# schematic.net
KiCad netlist of a schematic drawn in EAGLE
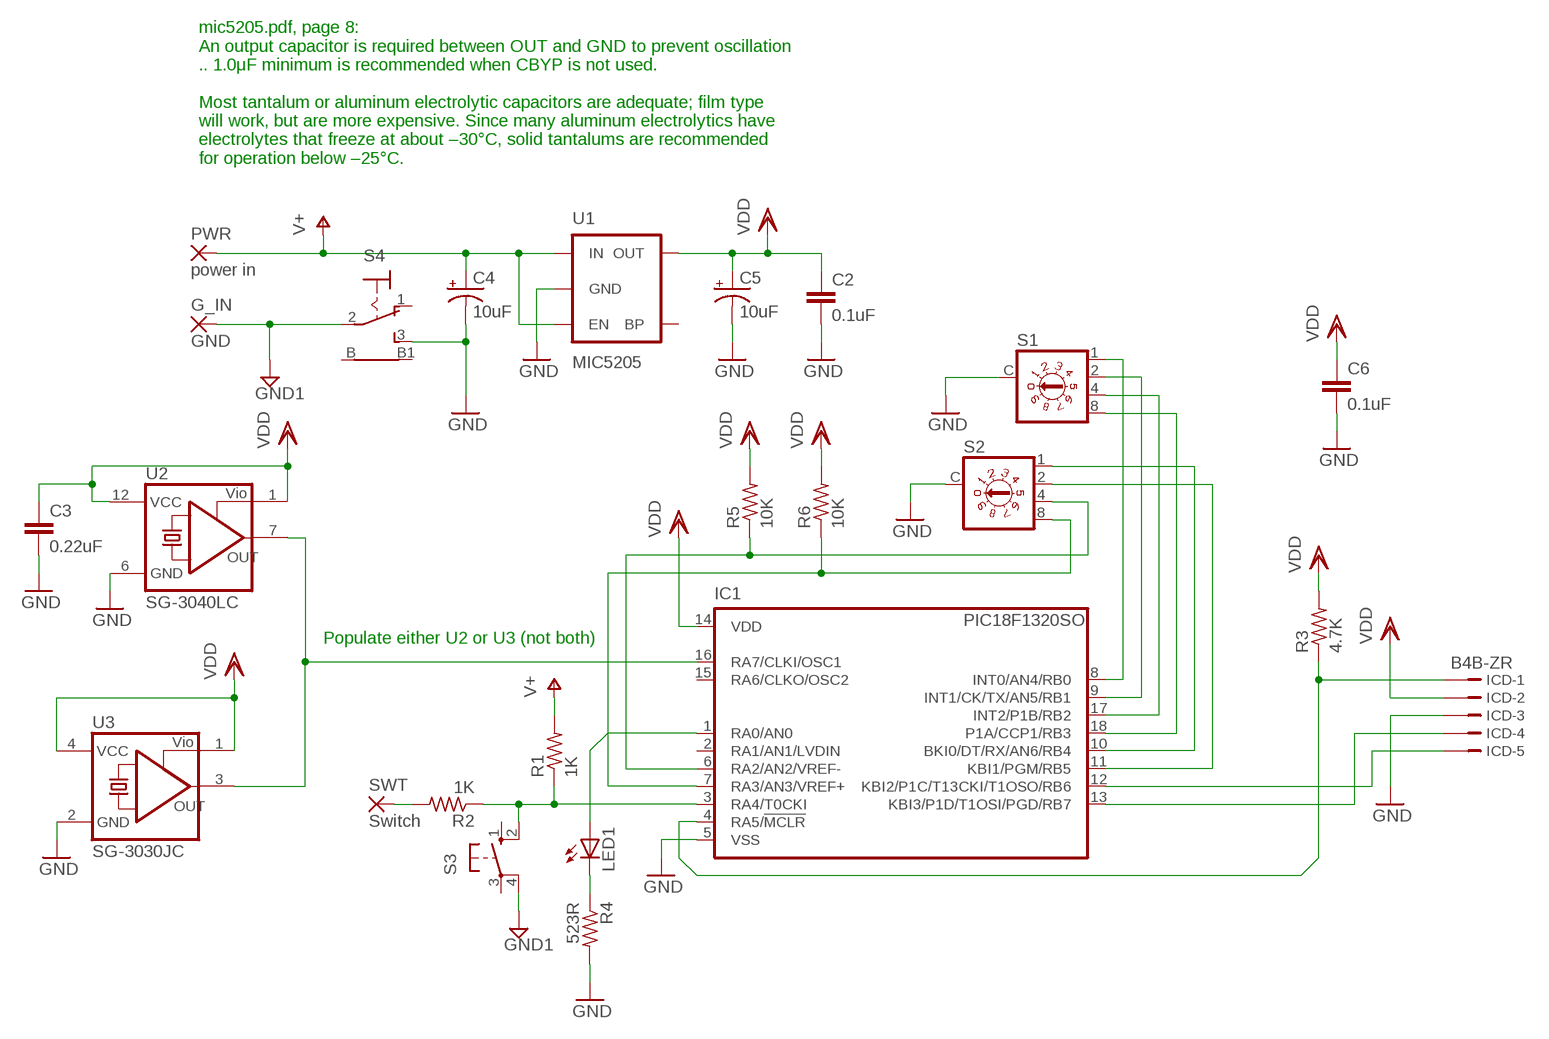
[diagram p0: schematic, sheet 1]

(export (version "E")
  (design (tool "Eeschema 10.0.6"))
  (components
    (comp (ref "C2")
      (value "0.1uF")
      (footprint "eagle-import:C2.5-3")
      (libsource (lib "eagle-import") (part "C2,5-3"))
    )
    (comp (ref "C3")
      (value "0.22uF")
      (footprint "eagle-import:C2.5-3")
      (libsource (lib "eagle-import") (part "C2,5-3"))
    )
    (comp (ref "C4")
      (value "10uF")
      (footprint "eagle-import:EIA3216")
      (libsource (lib "eagle-import") (part "CAP_POL1206"))
    )
    (comp (ref "C5")
      (value "10uF")
      (footprint "eagle-import:EIA3216")
      (libsource (lib "eagle-import") (part "CAP_POL1206"))
    )
    (comp (ref "C6")
      (value "0.1uF")
      (footprint "eagle-import:C2.5-3")
      (libsource (lib "eagle-import") (part "C2,5-3"))
    )
    (comp (ref "G_IN")
      (value "GND")
      (footprint "eagle-import:2,15_1,0")
      (libsource (lib "eagle-import") (part "2,15/1,0"))
    )
    (comp (ref "IC1")
      (value "PIC18F1320SO")
      (footprint "eagle-import:SO-18W")
      (fields (field (name "MF") "MICROCHIP") (field (name "MPN") "PIC18F1220-I/SO"))
      (libsource (lib "eagle-import") (part "PIC18F120SO2"))
    )
    (comp (ref "ICD")
      (value "B4B-ZR")
      (footprint "eagle-import:B5B-EH")
      (fields (field (name "MF") "FARNELL") (field (name "MPN") "B4B-ZR(LF)(SN)"))
      (libsource (lib "eagle-import") (part "?4B-ZRB"))
    )
    (comp (ref "LED1")
      (value "LED3MM")
      (footprint "eagle-import:LED3MM")
      (libsource (lib "eagle-import") (part "LED3MM"))
    )
    (comp (ref "PWR")
      (value "power in")
      (footprint "eagle-import:2,15_1,0")
      (libsource (lib "eagle-import") (part "2,15/1,0"))
    )
    (comp (ref "R1")
      (value "1K")
      (footprint "eagle-import:0204V")
      (libsource (lib "eagle-import") (part "R-US_0204/2V"))
    )
    (comp (ref "R2")
      (value "1K")
      (footprint "eagle-import:0204V")
      (libsource (lib "eagle-import") (part "R-US_0204/2V"))
    )
    (comp (ref "R3")
      (value "4.7K")
      (footprint "eagle-import:0204V")
      (libsource (lib "eagle-import") (part "R-US_0204/2V"))
    )
    (comp (ref "R4")
      (value "523R")
      (footprint "eagle-import:0204V")
      (libsource (lib "eagle-import") (part "R-US_0204/2V"))
    )
    (comp (ref "R5")
      (value "10K")
      (footprint "eagle-import:0204V")
      (libsource (lib "eagle-import") (part "R-US_0204/2V"))
    )
    (comp (ref "R6")
      (value "10K")
      (footprint "eagle-import:0204V")
      (libsource (lib "eagle-import") (part "R-US_0204/2V"))
    )
    (comp (ref "S1")
      (value "P101")
      (footprint "eagle-import:P101")
      (libsource (lib "eagle-import") (part "P101"))
    )
    (comp (ref "S2")
      (value "P101")
      (footprint "eagle-import:P101")
      (libsource (lib "eagle-import") (part "P101"))
    )
    (comp (ref "S3")
      (value "10-XX")
      (footprint "eagle-import:B3F-10XX")
      (fields (field (name "MPN") "B3F-1000"))
      (libsource (lib "eagle-import") (part "10-XX"))
    )
    (comp (ref "S4")
      (value "C&K_E101")
      (footprint "eagle-import:C&K_E101MD1ABE")
      (libsource (lib "eagle-import") (part "C&K_E101"))
    )
    (comp (ref "SWT")
      (value "Switch")
      (footprint "eagle-import:2,15_1,0")
      (libsource (lib "eagle-import") (part "2,15/1,0"))
    )
    (comp (ref "U1")
      (value "MIC5205")
      (footprint "eagle-import:SOT23-5")
      (libsource (lib "eagle-import") (part "V_REG_LDOSMD"))
    )
    (comp (ref "U2")
      (value "SG-3040LC")
      (footprint "eagle-import:SOJ-12-L")
      (libsource (lib "eagle-import") (part "SG-3030,40(LC,JC,JF)LC-LARGE"))
    )
    (comp (ref "U3")
      (value "SG-3030JC")
      (footprint "eagle-import:JC_TYPE")
      (libsource (lib "eagle-import") (part "SG-3030,40(LC,JC,JF)JC"))
    )
  )
  (nets
    (net (code "1") (name "GND") (class "Default")
      (node (ref "C2") (pin "2") (pinfunction "2_2") (pintype "passive"))
      (node (ref "C3") (pin "2") (pinfunction "2_2") (pintype "passive"))
      (node (ref "C4") (pin "C") (pinfunction "-_C") (pintype "passive"))
      (node (ref "C5") (pin "C") (pinfunction "-_C") (pintype "passive"))
      (node (ref "C6") (pin "2") (pinfunction "2_2") (pintype "passive"))
      (node (ref "IC1") (pin "5") (pinfunction "VSS_5") (pintype "power_in"))
      (node (ref "ICD") (pin "3") (pinfunction "1_3") (pintype "passive"))
      (node (ref "R4") (pin "2") (pinfunction "2_2") (pintype "passive"))
      (node (ref "S1") (pin "C") (pinfunction "C_C") (pintype "passive"))
      (node (ref "S2") (pin "C") (pinfunction "C_C") (pintype "passive"))
      (node (ref "S4") (pin "3") (pinfunction "S_3") (pintype "passive"))
      (node (ref "U1") (pin "2") (pinfunction "GND_2") (pintype "input"))
      (node (ref "U2") (pin "6") (pinfunction "GND_6") (pintype "power_in"))
      (node (ref "U3") (pin "2") (pinfunction "GND_2") (pintype "power_in"))
    )
    (net (code "2") (name "GND1") (class "Default")
      (node (ref "G_IN") (pin "1") (pinfunction "P_1") (pintype "passive"))
      (node (ref "S3") (pin "4") (pinfunction "P1_4") (pintype "passive"))
      (node (ref "S4") (pin "2") (pinfunction "P_2") (pintype "passive"))
    )
    (net (code "3") (name "Net-(IC1-BKI0{slash}DT{slash}RX{slash}AN6{slash}RB4)") (class "Default")
      (node (ref "IC1") (pin "10") (pinfunction "BKI0/DT/RX/AN6/RB4_10") (pintype "bidirectional"))
      (node (ref "S2") (pin "1") (pinfunction "1_1") (pintype "passive"))
    )
    (net (code "4") (name "Net-(IC1-INT0{slash}AN4{slash}RB0)") (class "Default")
      (node (ref "IC1") (pin "8") (pinfunction "INT0/AN4/RB0_8") (pintype "bidirectional"))
      (node (ref "S1") (pin "1") (pinfunction "1_1") (pintype "passive"))
    )
    (net (code "5") (name "Net-(IC1-INT1{slash}CK{slash}TX{slash}AN5{slash}RB1)") (class "Default")
      (node (ref "IC1") (pin "9") (pinfunction "INT1/CK/TX/AN5/RB1_9") (pintype "bidirectional"))
      (node (ref "S1") (pin "2") (pinfunction "2_2") (pintype "passive"))
    )
    (net (code "6") (name "Net-(IC1-INT2{slash}P1B{slash}RB2)") (class "Default")
      (node (ref "IC1") (pin "17") (pinfunction "INT2/P1B/RB2_17") (pintype "bidirectional"))
      (node (ref "S1") (pin "4") (pinfunction "4_4") (pintype "passive"))
    )
    (net (code "7") (name "Net-(IC1-KBI1{slash}PGM{slash}RB5)") (class "Default")
      (node (ref "IC1") (pin "11") (pinfunction "KBI1/PGM/RB5_11") (pintype "bidirectional"))
      (node (ref "S2") (pin "2") (pinfunction "2_2") (pintype "passive"))
    )
    (net (code "8") (name "Net-(IC1-KBI2{slash}P1C{slash}T13CKI{slash}T1OSO{slash}RB6)") (class "Default")
      (node (ref "IC1") (pin "12") (pinfunction "KBI2/P1C/T13CKI/T1OSO/RB6_12") (pintype "bidirectional"))
      (node (ref "ICD") (pin "5") (pinfunction "1_5") (pintype "passive"))
    )
    (net (code "9") (name "Net-(IC1-KBI3{slash}P1D{slash}T1OSI{slash}PGD{slash}RB7)") (class "Default")
      (node (ref "IC1") (pin "13") (pinfunction "KBI3/P1D/T1OSI/PGD/RB7_13") (pintype "bidirectional"))
      (node (ref "ICD") (pin "4") (pinfunction "1_4") (pintype "passive"))
    )
    (net (code "10") (name "Net-(IC1-P1A{slash}CCP1{slash}RB3)") (class "Default")
      (node (ref "IC1") (pin "18") (pinfunction "P1A/CCP1/RB3_18") (pintype "bidirectional"))
      (node (ref "S1") (pin "8") (pinfunction "8_8") (pintype "passive"))
    )
    (net (code "11") (name "Net-(IC1-RA0{slash}AN0)") (class "Default")
      (node (ref "IC1") (pin "1") (pinfunction "RA0/AN0_1") (pintype "bidirectional"))
      (node (ref "LED1") (pin "A") (pinfunction "A_A") (pintype "passive"))
    )
    (net (code "12") (name "Net-(IC1-RA2{slash}AN2{slash}VREF-)") (class "Default")
      (node (ref "IC1") (pin "6") (pinfunction "RA2/AN2/VREF-_6") (pintype "bidirectional"))
      (node (ref "R5") (pin "1") (pinfunction "1_1") (pintype "passive"))
      (node (ref "S2") (pin "4") (pinfunction "4_4") (pintype "passive"))
    )
    (net (code "13") (name "Net-(IC1-RA3{slash}AN3{slash}VREF+)") (class "Default")
      (node (ref "IC1") (pin "7") (pinfunction "RA3/AN3/VREF+_7") (pintype "bidirectional"))
      (node (ref "R6") (pin "1") (pinfunction "1_1") (pintype "passive"))
      (node (ref "S2") (pin "8") (pinfunction "8_8") (pintype "passive"))
    )
    (net (code "14") (name "Net-(IC1-RA4{slash}T0CKI)") (class "Default")
      (node (ref "IC1") (pin "3") (pinfunction "RA4/T0CKI_3") (pintype "bidirectional"))
      (node (ref "R1") (pin "1") (pinfunction "1_1") (pintype "passive"))
      (node (ref "R2") (pin "1") (pinfunction "1_1") (pintype "passive"))
      (node (ref "S3") (pin "2") (pinfunction "S1_2") (pintype "passive"))
    )
    (net (code "15") (name "Net-(IC1-RA5{slash}~{MCLR})") (class "Default")
      (node (ref "IC1") (pin "4") (pinfunction "RA5/~{MCLR}_4") (pintype "input"))
      (node (ref "ICD") (pin "1") (pinfunction "1_1") (pintype "passive"))
      (node (ref "R3") (pin "1") (pinfunction "1_1") (pintype "passive"))
    )
    (net (code "16") (name "Net-(IC1-RA7{slash}CLKI{slash}OSC1)") (class "Default")
      (node (ref "IC1") (pin "16") (pinfunction "RA7/CLKI/OSC1_16") (pintype "bidirectional"))
      (node (ref "U2") (pin "7") (pinfunction "OUT_7") (pintype "output"))
      (node (ref "U3") (pin "3") (pinfunction "OUT_3") (pintype "output"))
    )
    (net (code "17") (name "Net-(LED1-C)") (class "Default")
      (node (ref "LED1") (pin "K") (pinfunction "C_K") (pintype "passive"))
      (node (ref "R4") (pin "1") (pinfunction "1_1") (pintype "passive"))
    )
    (net (code "18") (name "Net-(SWT-P)") (class "Default")
      (node (ref "R2") (pin "2") (pinfunction "2_2") (pintype "passive"))
      (node (ref "SWT") (pin "1") (pinfunction "P_1") (pintype "passive"))
    )
    (net (code "19") (name "V+") (class "Default")
      (node (ref "C4") (pin "A") (pinfunction "+_A") (pintype "passive"))
      (node (ref "PWR") (pin "1") (pinfunction "P_1") (pintype "passive"))
      (node (ref "R1") (pin "2") (pinfunction "2_2") (pintype "passive"))
      (node (ref "U1") (pin "1") (pinfunction "IN_1") (pintype "input"))
      (node (ref "U1") (pin "3") (pinfunction "EN_3") (pintype "input"))
    )
    (net (code "20") (name "VDD") (class "Default")
      (node (ref "C2") (pin "1") (pinfunction "1_1") (pintype "passive"))
      (node (ref "C3") (pin "1") (pinfunction "1_1") (pintype "passive"))
      (node (ref "C5") (pin "A") (pinfunction "+_A") (pintype "passive"))
      (node (ref "C6") (pin "1") (pinfunction "1_1") (pintype "passive"))
      (node (ref "IC1") (pin "14") (pinfunction "VDD_14") (pintype "power_in"))
      (node (ref "ICD") (pin "2") (pinfunction "1_2") (pintype "passive"))
      (node (ref "R3") (pin "2") (pinfunction "2_2") (pintype "passive"))
      (node (ref "R5") (pin "2") (pinfunction "2_2") (pintype "passive"))
      (node (ref "R6") (pin "2") (pinfunction "2_2") (pintype "passive"))
      (node (ref "U1") (pin "5") (pinfunction "OUT_5") (pintype "passive"))
      (node (ref "U2") (pin "1") (pinfunction "VIO_1") (pintype "input"))
      (node (ref "U2") (pin "12") (pinfunction "VCC_12") (pintype "power_in"))
      (node (ref "U3") (pin "1") (pinfunction "VIO_1") (pintype "input"))
      (node (ref "U3") (pin "4") (pinfunction "VCC_4") (pintype "power_in"))
    )
    (net (code "21") (name "unconnected-(IC1-RA1{slash}AN1{slash}LVDIN-Pad2)") (class "Default")
      (node (ref "IC1") (pin "2") (pinfunction "RA1/AN1/LVDIN_2") (pintype "bidirectional"))
    )
    (net (code "22") (name "unconnected-(IC1-RA6{slash}CLKO{slash}OSC2-Pad15)") (class "Default")
      (node (ref "IC1") (pin "15") (pinfunction "RA6/CLKO/OSC2_15") (pintype "bidirectional"))
    )
    (net (code "23") (name "unconnected-(S3-P-Pad3)") (class "Default")
      (node (ref "S3") (pin "3") (pinfunction "P_3") (pintype "passive"))
    )
    (net (code "24") (name "unconnected-(S3-S-Pad1)") (class "Default")
      (node (ref "S3") (pin "1") (pinfunction "S_1") (pintype "passive"))
    )
    (net (code "25") (name "unconnected-(S4-O-Pad1)") (class "Default")
      (node (ref "S4") (pin "1") (pinfunction "O_1") (pintype "passive"))
    )
    (net (code "26") (name "unconnected-(S4-PadB)") (class "Default")
      (node (ref "S4") (pin "B") (pinfunction "B_B") (pintype "passive"))
    )
    (net (code "27") (name "unconnected-(S4-PadB1)") (class "Default")
      (node (ref "S4") (pin "B1") (pinfunction "B1_B1") (pintype "passive"))
    )
    (net (code "28") (name "unconnected-(U1-BP-Pad4)") (class "Default")
      (node (ref "U1") (pin "4") (pinfunction "BP_4") (pintype "input"))
    )
  )
)
